# LightSwitch3.net
KiCad netlist of a schematic drawn in EAGLE
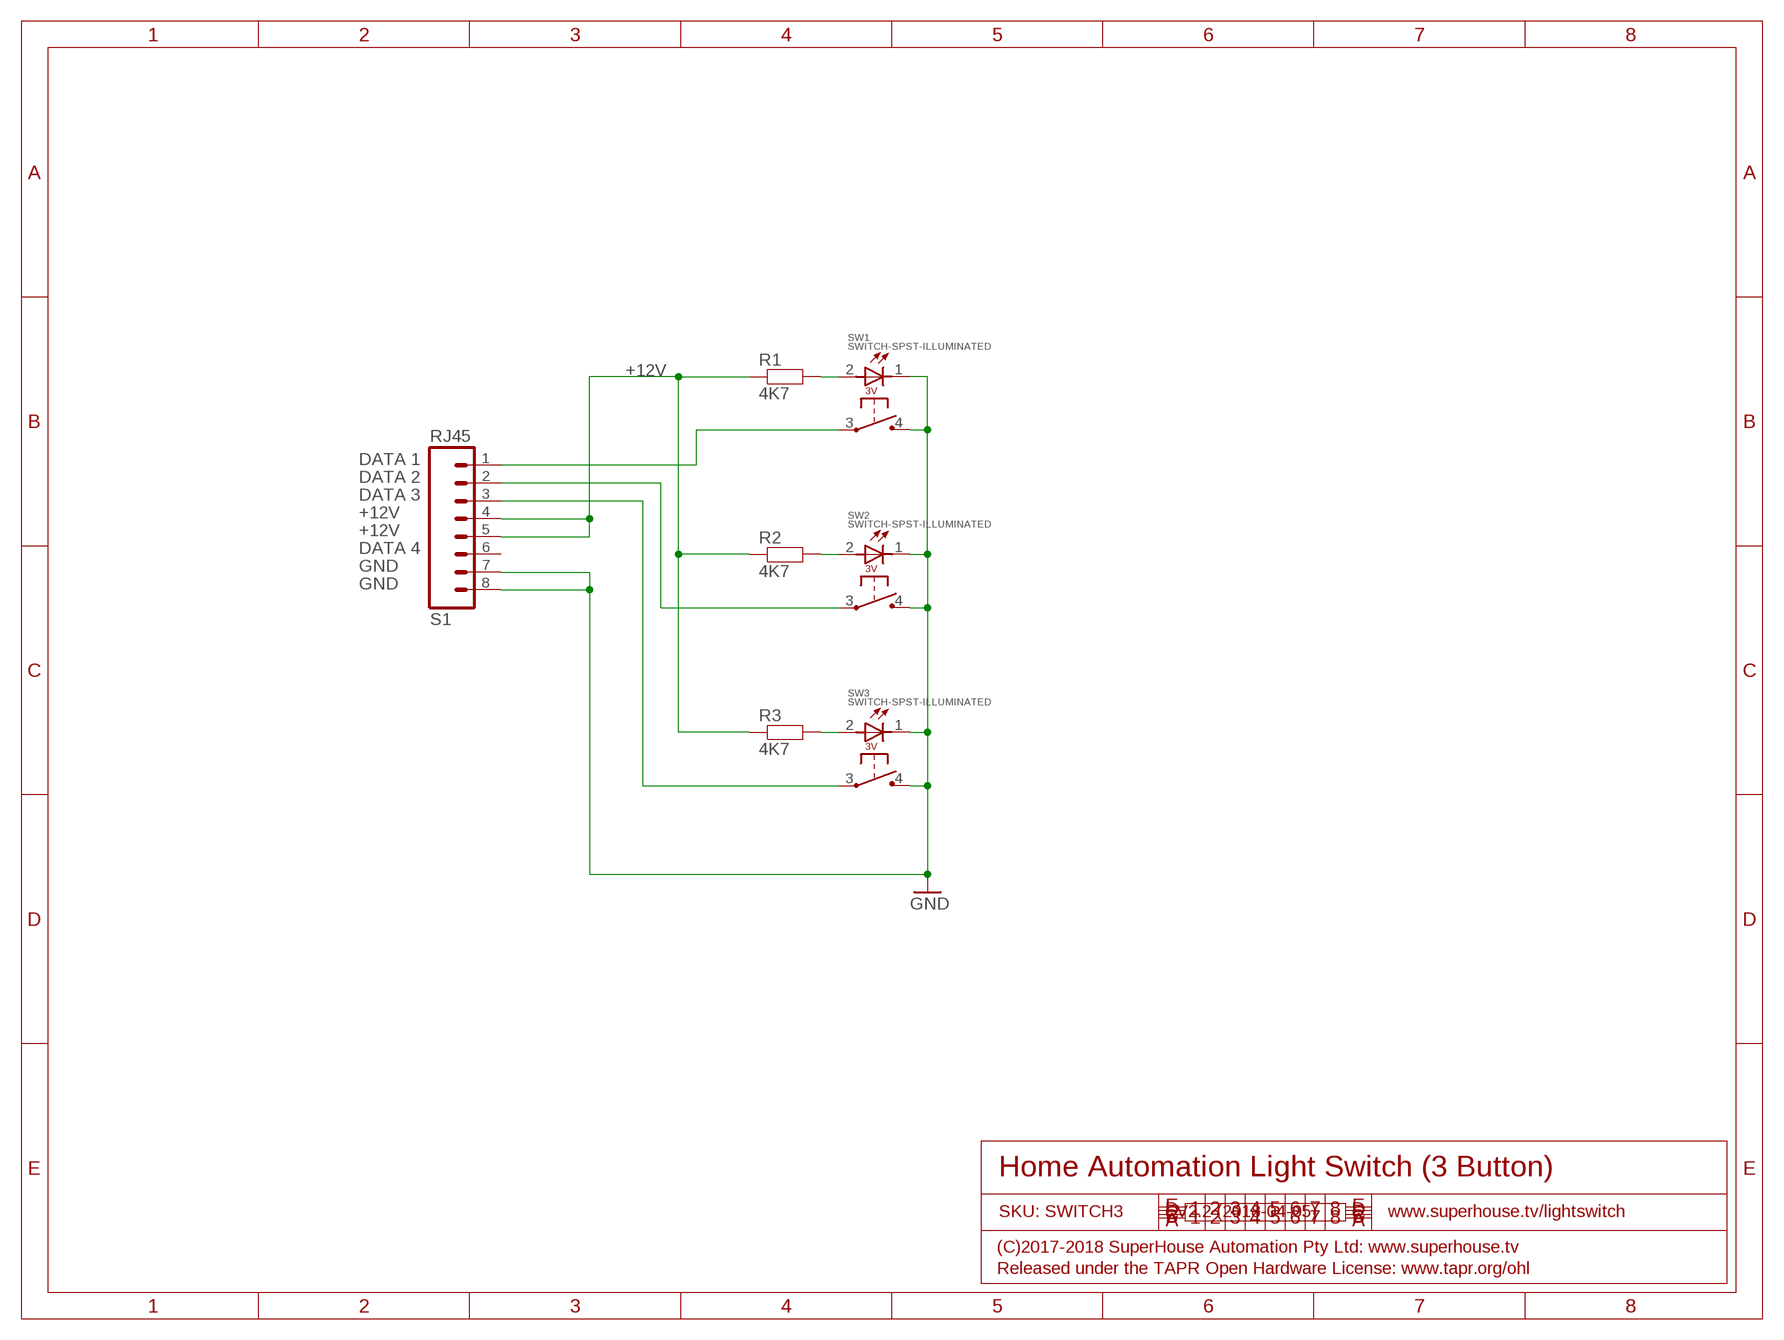
[diagram p0: schematic, sheet 1]

(export (version "E")
  (design (tool "Eeschema 10.0.6"))
  (components
    (comp (ref "R1")
      (value "4K7")
      (footprint "eagle-import:0603")
      (libsource (lib "eagle-import") (part "RESISTOR0603"))
    )
    (comp (ref "R2")
      (value "4K7")
      (footprint "eagle-import:0603")
      (libsource (lib "eagle-import") (part "RESISTOR0603"))
    )
    (comp (ref "R3")
      (value "4K7")
      (footprint "eagle-import:0603")
      (libsource (lib "eagle-import") (part "RESISTOR0603"))
    )
    (comp (ref "S1")
      (value "RJ45")
      (footprint "eagle-import:RJ45")
      (libsource (lib "eagle-import") (part "RJ45"))
    )
    (comp (ref "SW1")
      (value "SWITCH-SPST-ILLUMINATED")
      (footprint "eagle-import:SWITCH-SPST-ILLUMINATED")
      (libsource (lib "eagle-import") (part "SWITCH-SPST-ILLUMINATED"))
    )
    (comp (ref "SW2")
      (value "SWITCH-SPST-ILLUMINATED")
      (footprint "eagle-import:SWITCH-SPST-ILLUMINATED")
      (libsource (lib "eagle-import") (part "SWITCH-SPST-ILLUMINATED"))
    )
    (comp (ref "SW3")
      (value "SWITCH-SPST-ILLUMINATED")
      (footprint "eagle-import:SWITCH-SPST-ILLUMINATED")
      (libsource (lib "eagle-import") (part "SWITCH-SPST-ILLUMINATED"))
    )
  )
  (nets
    (net (code "1") (name "/+12V") (class "Default")
      (node (ref "R1") (pin "1") (pinfunction "1_1") (pintype "passive"))
      (node (ref "R2") (pin "1") (pinfunction "1_1") (pintype "passive"))
      (node (ref "R3") (pin "1") (pinfunction "1_1") (pintype "passive"))
      (node (ref "S1") (pin "4") (pinfunction "4_4") (pintype "passive"))
      (node (ref "S1") (pin "5") (pinfunction "5_5") (pintype "passive"))
    )
    (net (code "2") (name "GND") (class "Default")
      (node (ref "S1") (pin "7") (pinfunction "7_7") (pintype "passive"))
      (node (ref "S1") (pin "8") (pinfunction "8_8") (pintype "passive"))
      (node (ref "SW1") (pin "1") (pinfunction "-_1") (pintype "passive"))
      (node (ref "SW1") (pin "4") (pinfunction "NO_4") (pintype "passive"))
      (node (ref "SW2") (pin "1") (pinfunction "-_1") (pintype "passive"))
      (node (ref "SW2") (pin "4") (pinfunction "NO_4") (pintype "passive"))
      (node (ref "SW3") (pin "1") (pinfunction "-_1") (pintype "passive"))
      (node (ref "SW3") (pin "4") (pinfunction "NO_4") (pintype "passive"))
    )
    (net (code "3") (name "Net-(SW1-+)") (class "Default")
      (node (ref "R1") (pin "2") (pinfunction "2_2") (pintype "passive"))
      (node (ref "SW1") (pin "2") (pinfunction "+_2") (pintype "passive"))
    )
    (net (code "4") (name "Net-(SW1-COM)") (class "Default")
      (node (ref "S1") (pin "1") (pinfunction "1_1") (pintype "passive"))
      (node (ref "SW1") (pin "3") (pinfunction "COM_3") (pintype "passive"))
    )
    (net (code "5") (name "Net-(SW2-+)") (class "Default")
      (node (ref "R2") (pin "2") (pinfunction "2_2") (pintype "passive"))
      (node (ref "SW2") (pin "2") (pinfunction "+_2") (pintype "passive"))
    )
    (net (code "6") (name "Net-(SW2-COM)") (class "Default")
      (node (ref "S1") (pin "2") (pinfunction "2_2") (pintype "passive"))
      (node (ref "SW2") (pin "3") (pinfunction "COM_3") (pintype "passive"))
    )
    (net (code "7") (name "Net-(SW3-+)") (class "Default")
      (node (ref "R3") (pin "2") (pinfunction "2_2") (pintype "passive"))
      (node (ref "SW3") (pin "2") (pinfunction "+_2") (pintype "passive"))
    )
    (net (code "8") (name "Net-(SW3-COM)") (class "Default")
      (node (ref "S1") (pin "3") (pinfunction "3_3") (pintype "passive"))
      (node (ref "SW3") (pin "3") (pinfunction "COM_3") (pintype "passive"))
    )
    (net (code "9") (name "unconnected-(S1-Pad6)") (class "Default")
      (node (ref "S1") (pin "6") (pinfunction "6_6") (pintype "passive"))
    )
  )
)
